# LED_Panel_And_Driver.net
KiCad netlist of a schematic drawn in EAGLE
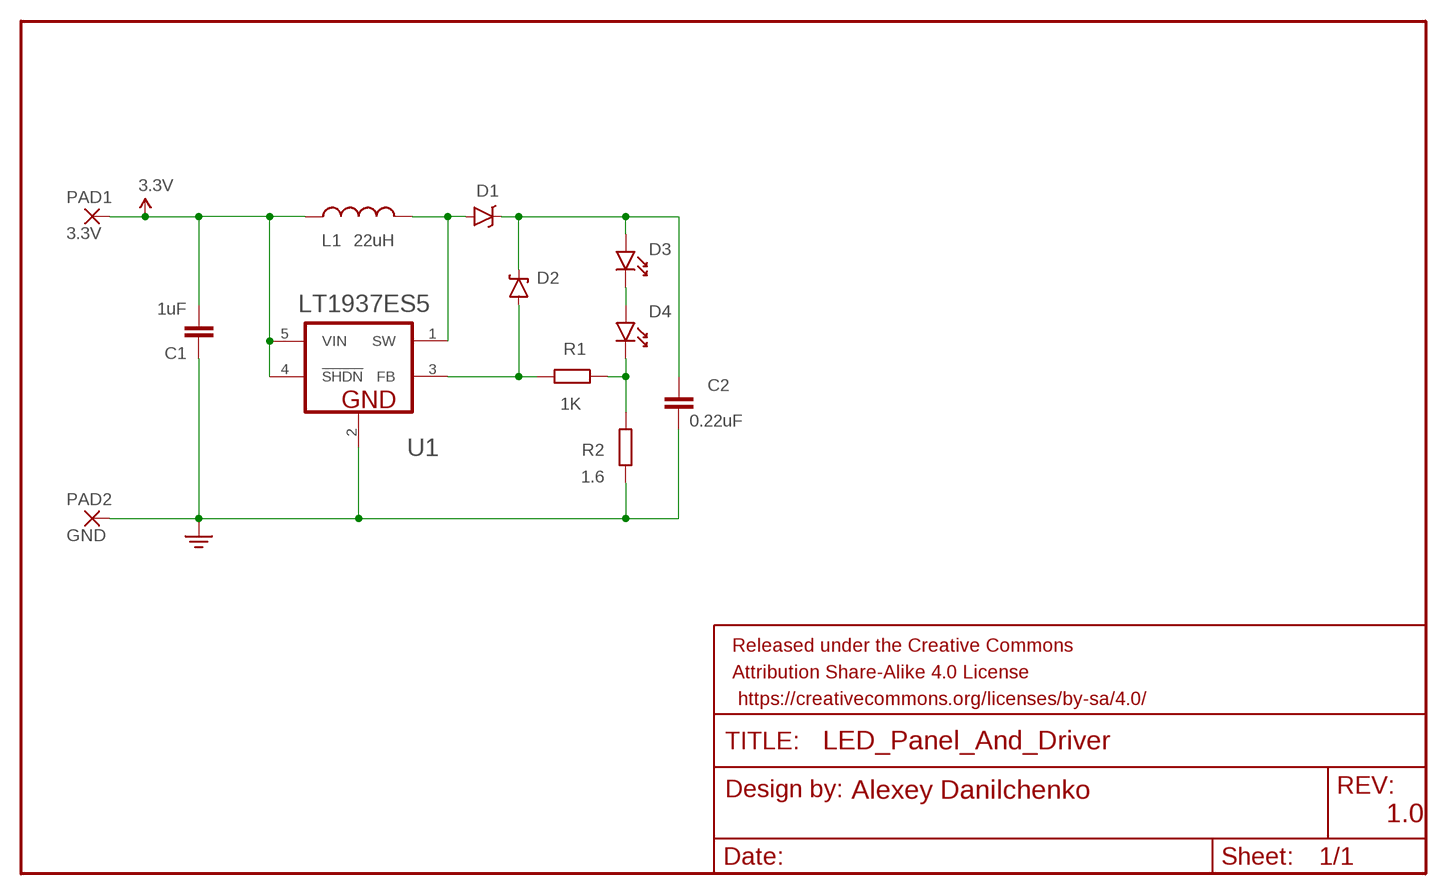
[diagram p0: schematic, sheet 1]

(export (version "E")
  (design (tool "Eeschema 10.0.6"))
  (components
    (comp (ref "C1")
      (value "1uF")
      (footprint "eagle-import:C0805")
      (libsource (lib "eagle-import") (part "C-EUC0805"))
    )
    (comp (ref "C2")
      (value "0.22uF")
      (footprint "eagle-import:0603-CAP")
      (libsource (lib "eagle-import") (part "CAP0603-CAP"))
    )
    (comp (ref "D1")
      (value "RB751")
      (footprint "eagle-import:SOD-523")
      (libsource (lib "eagle-import") (part "DIODE-SCHOTTKY-RB751"))
    )
    (comp (ref "D2")
      (value "DIODE-ZENER")
      (footprint "eagle-import:SOD-923")
      (libsource (lib "eagle-import") (part "DIODE-ZENER"))
    )
    (comp (ref "D3")
      (value "YUJI_2835_SMD")
      (footprint "eagle-import:2835_SMD")
      (libsource (lib "eagle-import") (part "YUJI_2835_SMD"))
    )
    (comp (ref "D4")
      (value "YUJI_2835_SMD")
      (footprint "eagle-import:2835_SMD")
      (libsource (lib "eagle-import") (part "YUJI_2835_SMD"))
    )
    (comp (ref "FRAME1")
      (value "FRAME-LEDGER")
      (footprint "eagle-import:CREATIVE_COMMONS")
      (fields (field (name "AUTHOR") "Alexey Danilchenko") (field (name "VER") "1.0"))
      (libsource (lib "eagle-import") (part "FRAME-LEDGER"))
    )
    (comp (ref "L1")
      (value "22uH")
      (footprint "eagle-import:1210")
      (libsource (lib "eagle-import") (part "INDUCTOR1210"))
    )
    (comp (ref "PAD1")
      (value "3.3V")
      (footprint "eagle-import:SMD2,54-5,08")
      (libsource (lib "eagle-import") (part "SMD5"))
    )
    (comp (ref "PAD2")
      (value "GND")
      (footprint "eagle-import:SMD2,54-5,08")
      (libsource (lib "eagle-import") (part "SMD5"))
    )
    (comp (ref "R1")
      (value "1K")
      (footprint "eagle-import:R0805")
      (libsource (lib "eagle-import") (part "R-EU_R0805"))
    )
    (comp (ref "R2")
      (value "1.6")
      (footprint "eagle-import:M1206")
      (libsource (lib "eagle-import") (part "rcl_334_R-EU_M1206"))
    )
    (comp (ref "U1")
      (value "LT1937ES5")
      (footprint "eagle-import:LINEAR_TECHNOLOGY_LT1937ES5#TRMPBF_1")
      (fields (field (name "MF") "Linear Technology") (field (name "MPN") "LT1937ES5#TRMPBF"))
      (libsource (lib "eagle-import") (part "LINEAR_TECHNOLOGY_LT1937ES5#TRMPBFLINEAR_TECHNOLOGY_LT1937ES5#TRMPBF_0_1"))
    )
  )
  (nets
    (net (code "1") (name "3.3V") (class "Default")
      (node (ref "C1") (pin "1") (pinfunction "1_1") (pintype "passive"))
      (node (ref "L1") (pin "1") (pinfunction "1_1") (pintype "passive"))
      (node (ref "PAD1") (pin "1") (pinfunction "P_1") (pintype "passive"))
      (node (ref "U1") (pin "4") (pinfunction "~{SHDN}_4") (pintype "input"))
      (node (ref "U1") (pin "5") (pinfunction "VIN_5") (pintype "power_in"))
    )
    (net (code "2") (name "GND") (class "Default")
      (node (ref "C1") (pin "2") (pinfunction "2_2") (pintype "passive"))
      (node (ref "C2") (pin "2") (pinfunction "2_2") (pintype "passive"))
      (node (ref "PAD2") (pin "1") (pinfunction "P_1") (pintype "passive"))
      (node (ref "R2") (pin "1") (pinfunction "1_1") (pintype "passive"))
      (node (ref "U1") (pin "2") (pinfunction "GND_2") (pintype "power_in"))
    )
    (net (code "3") (name "Net-(C2-Pad1)") (class "Default")
      (node (ref "C2") (pin "1") (pinfunction "1_1") (pintype "passive"))
      (node (ref "D1") (pin "C") (pinfunction "C_C") (pintype "passive"))
      (node (ref "D2") (pin "C") (pinfunction "C_C") (pintype "passive"))
      (node (ref "D3") (pin "ANODE") (pinfunction "ANODE_ANODE") (pintype "bidirectional"))
    )
    (net (code "4") (name "Net-(D3-PadCATHODE)") (class "Default")
      (node (ref "D3") (pin "CATHODE") (pinfunction "CATHODE_CATHODE") (pintype "bidirectional"))
      (node (ref "D4") (pin "ANODE") (pinfunction "ANODE_ANODE") (pintype "bidirectional"))
    )
    (net (code "5") (name "Net-(D4-PadCATHODE)") (class "Default")
      (node (ref "D4") (pin "CATHODE") (pinfunction "CATHODE_CATHODE") (pintype "bidirectional"))
      (node (ref "R1") (pin "1") (pinfunction "1_1") (pintype "passive"))
      (node (ref "R2") (pin "2") (pinfunction "2_2") (pintype "passive"))
    )
    (net (code "6") (name "Net-(U1-FB)") (class "Default")
      (node (ref "D2") (pin "A") (pinfunction "A_A") (pintype "passive"))
      (node (ref "R1") (pin "2") (pinfunction "2_2") (pintype "passive"))
      (node (ref "U1") (pin "3") (pinfunction "FB_3") (pintype "input"))
    )
    (net (code "7") (name "Net-(U1-SW)") (class "Default")
      (node (ref "D1") (pin "A") (pinfunction "A_A") (pintype "passive"))
      (node (ref "L1") (pin "2") (pinfunction "2_2") (pintype "passive"))
      (node (ref "U1") (pin "1") (pinfunction "SW_1") (pintype "power_in"))
    )
  )
)
